# SushiBitsCamera.net
KiCad netlist of a schematic drawn in EAGLE
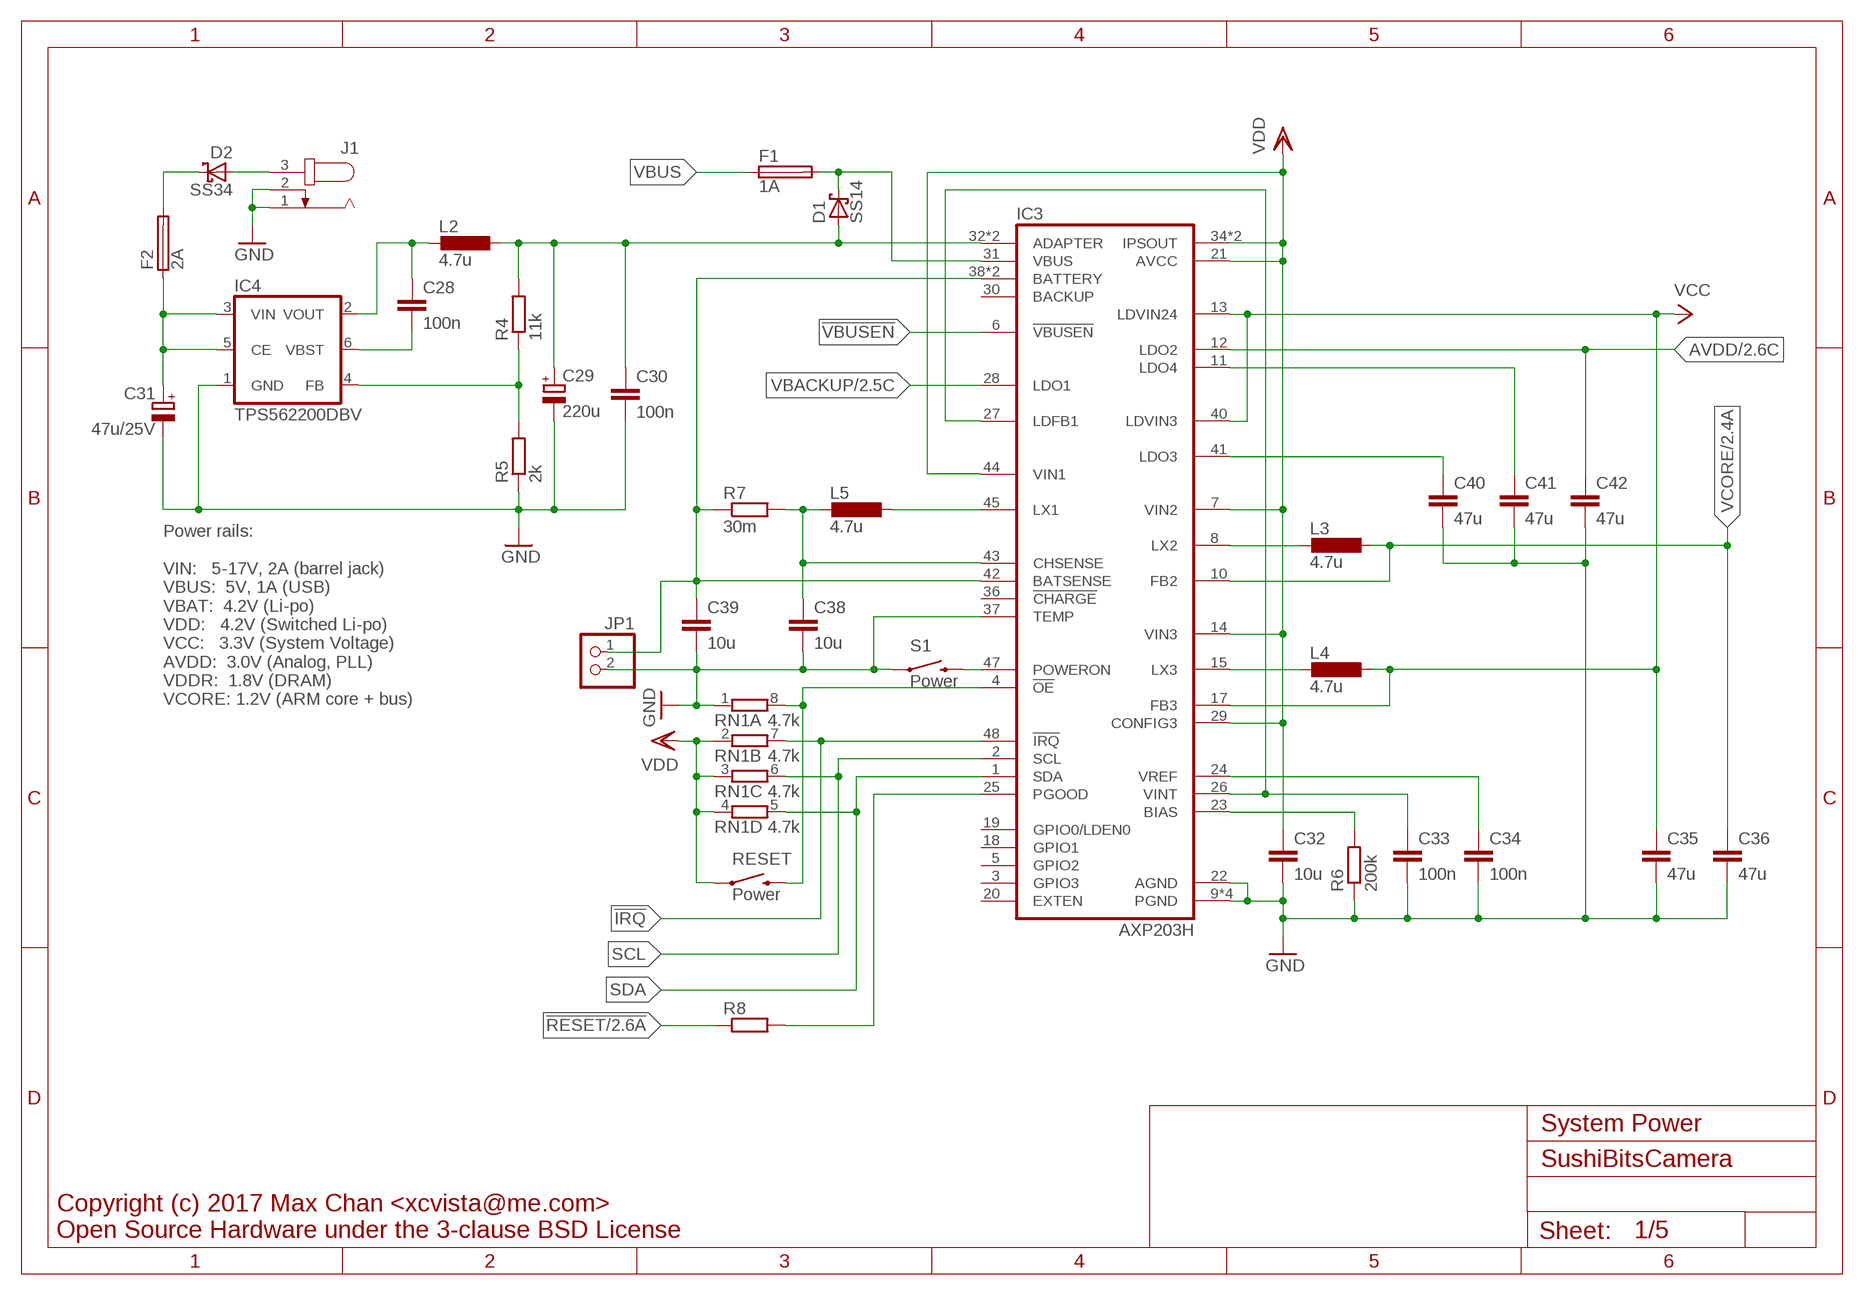
[diagram p0: schematic, sheet 1]
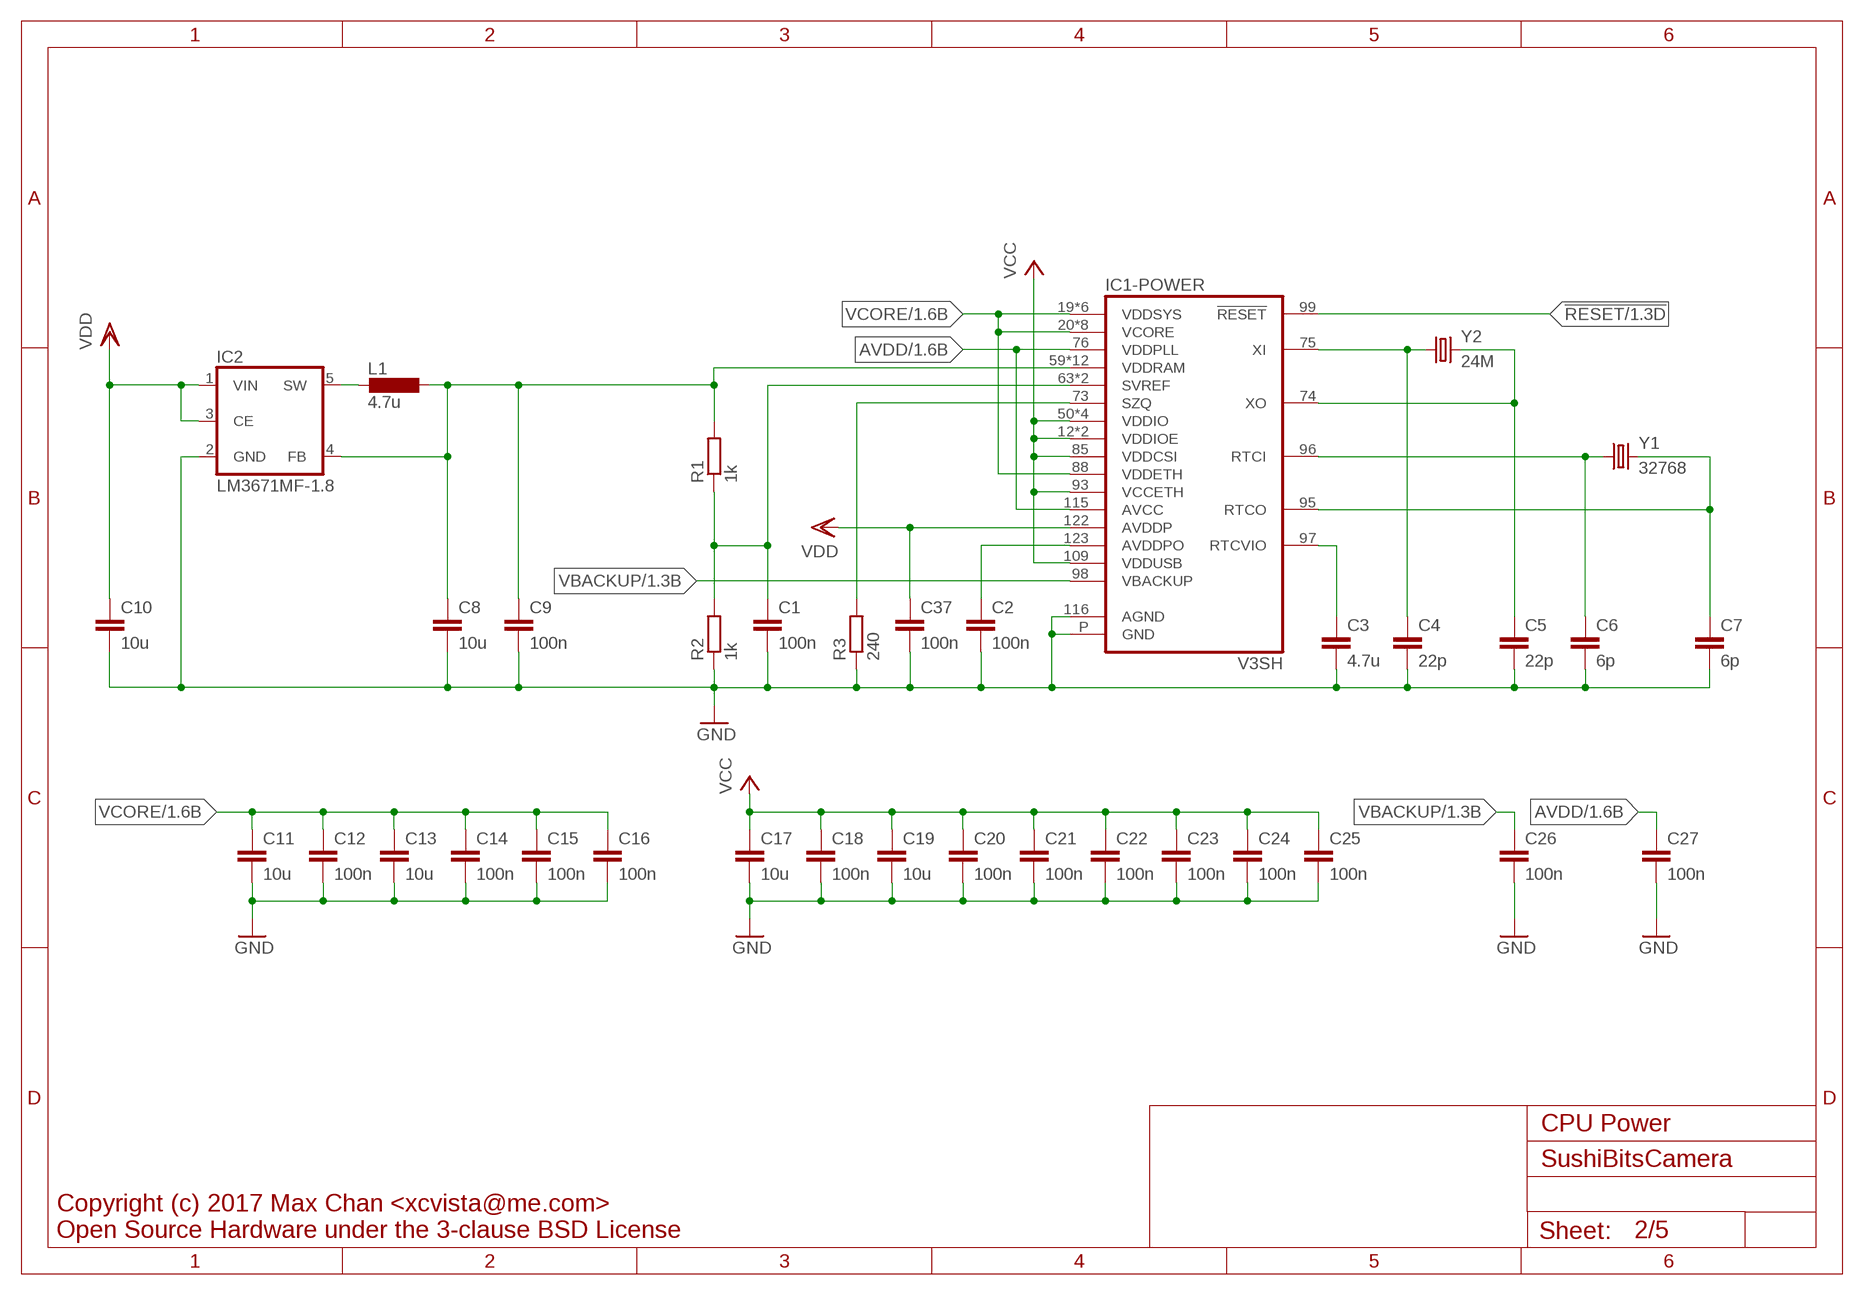
[diagram p1: schematic, sheet 2]
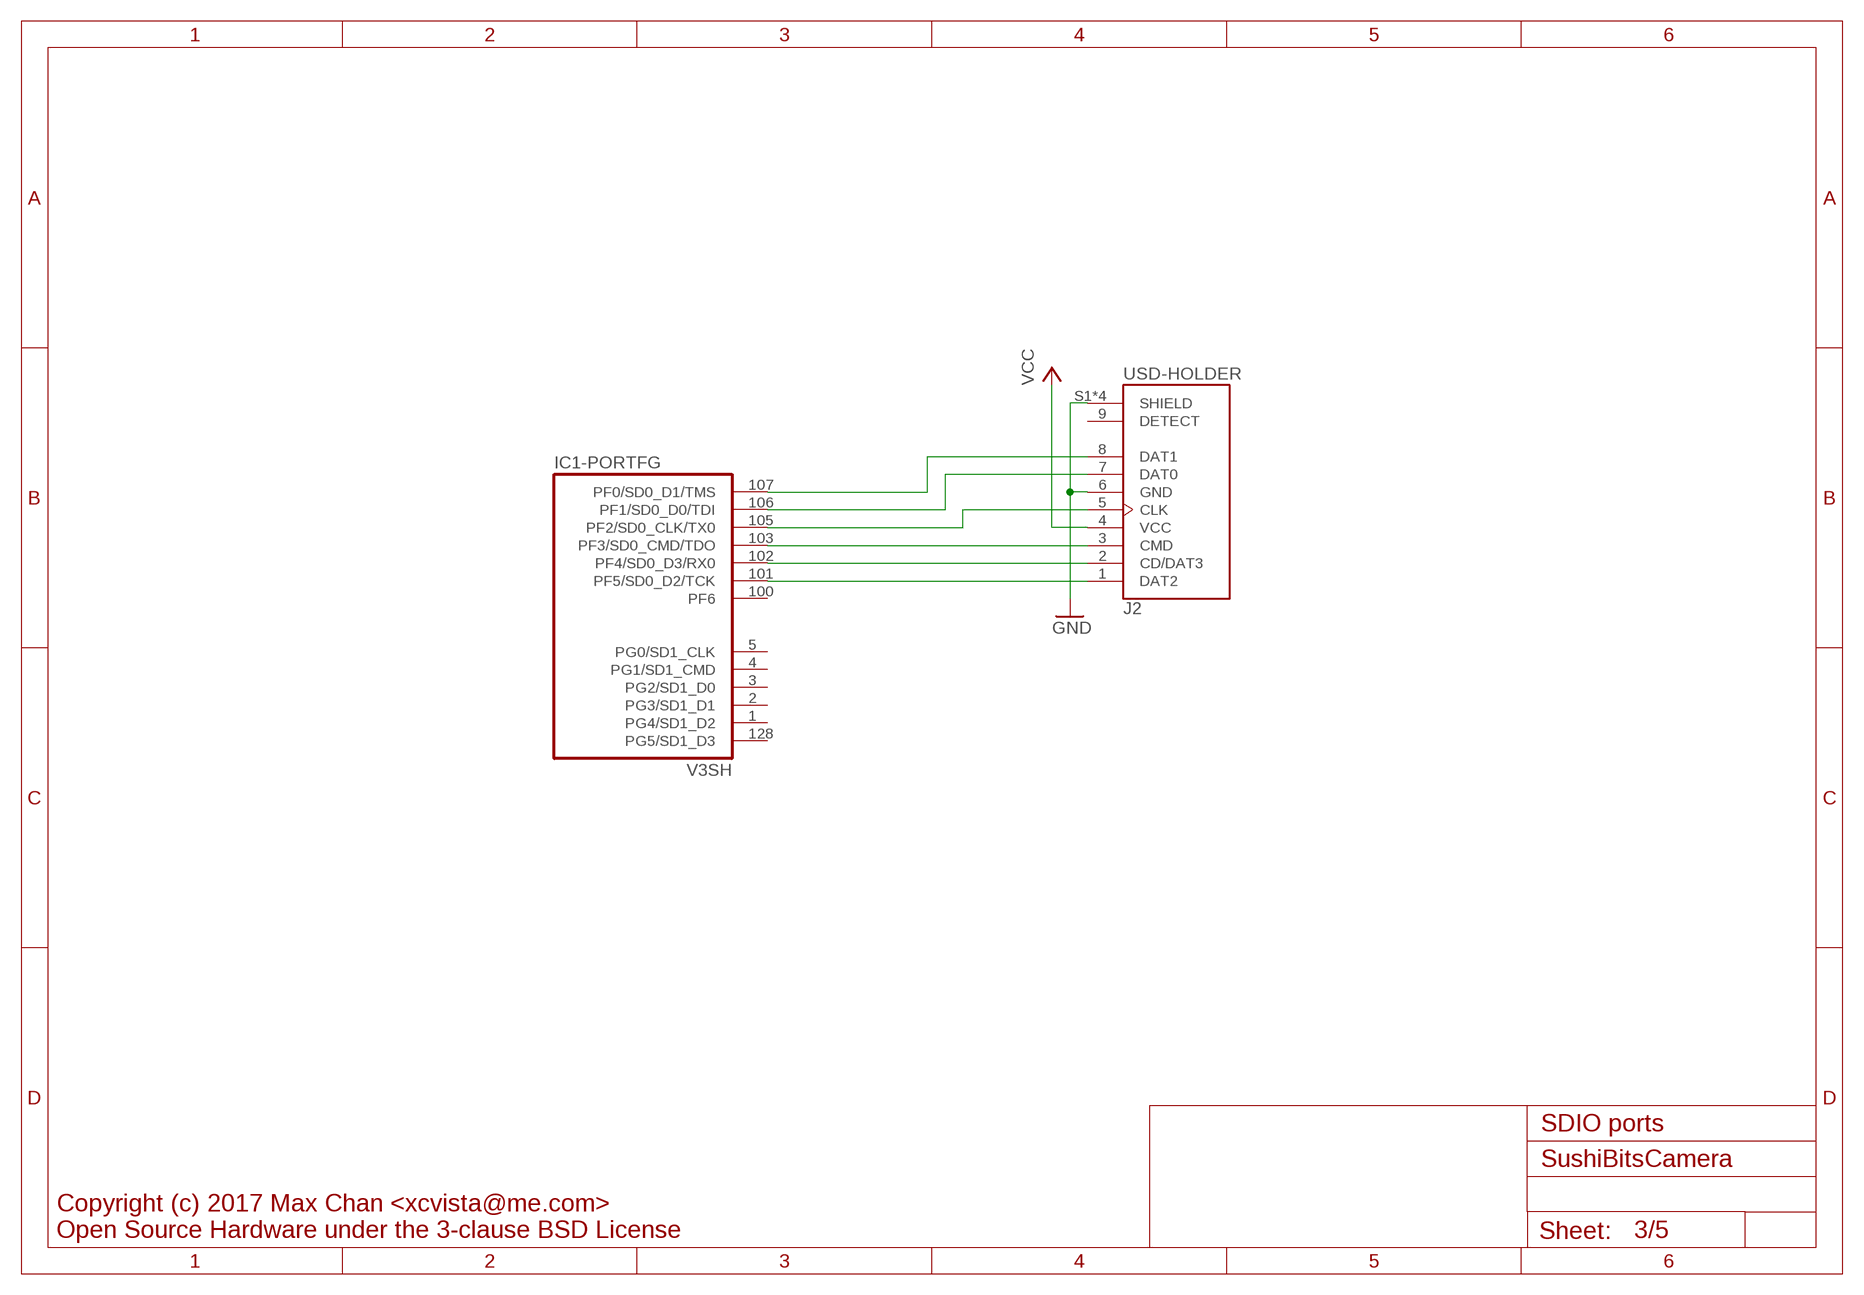
[diagram p2: schematic, sheet 3]
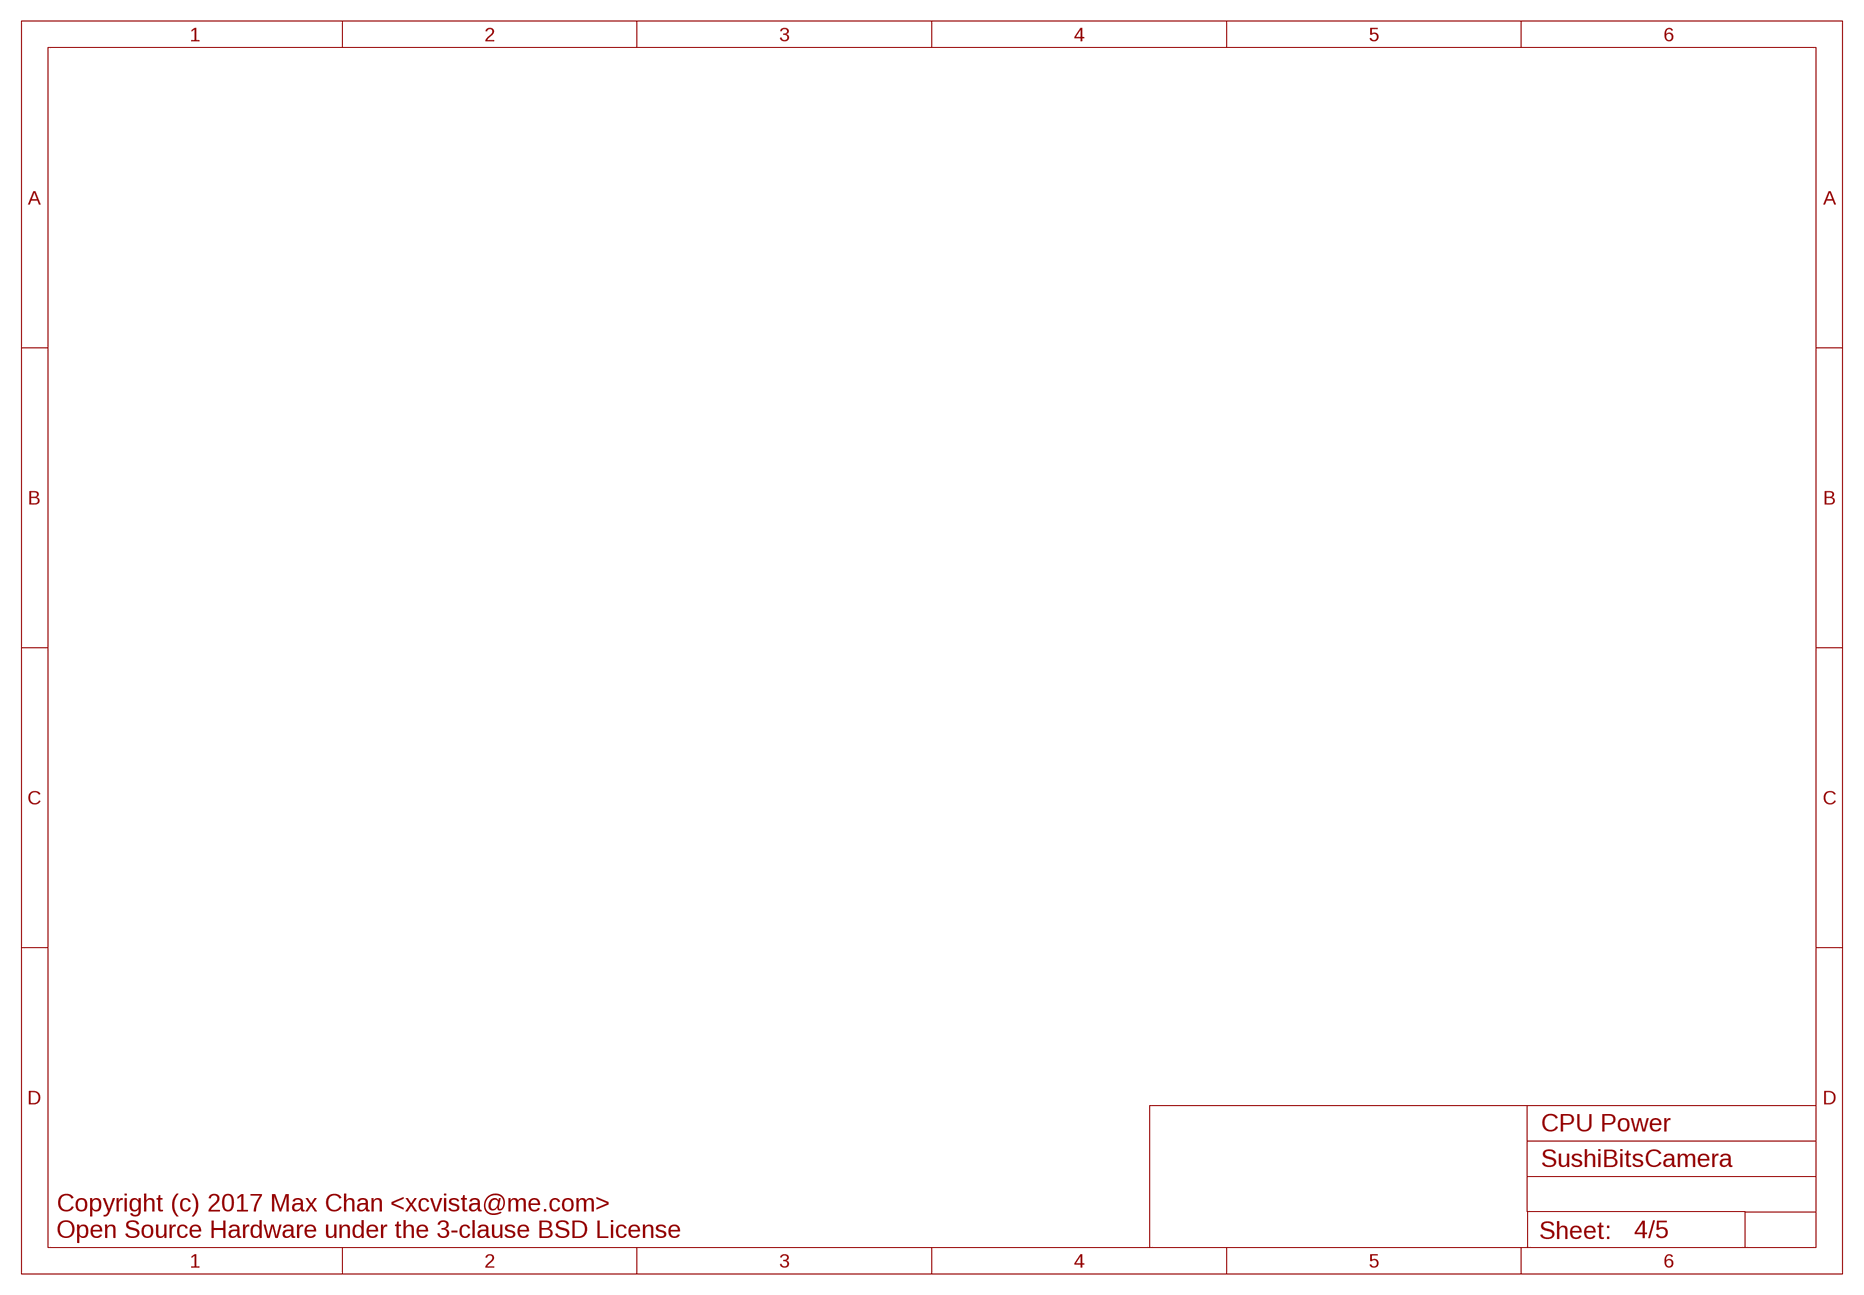
[diagram p3: schematic, sheet 4]
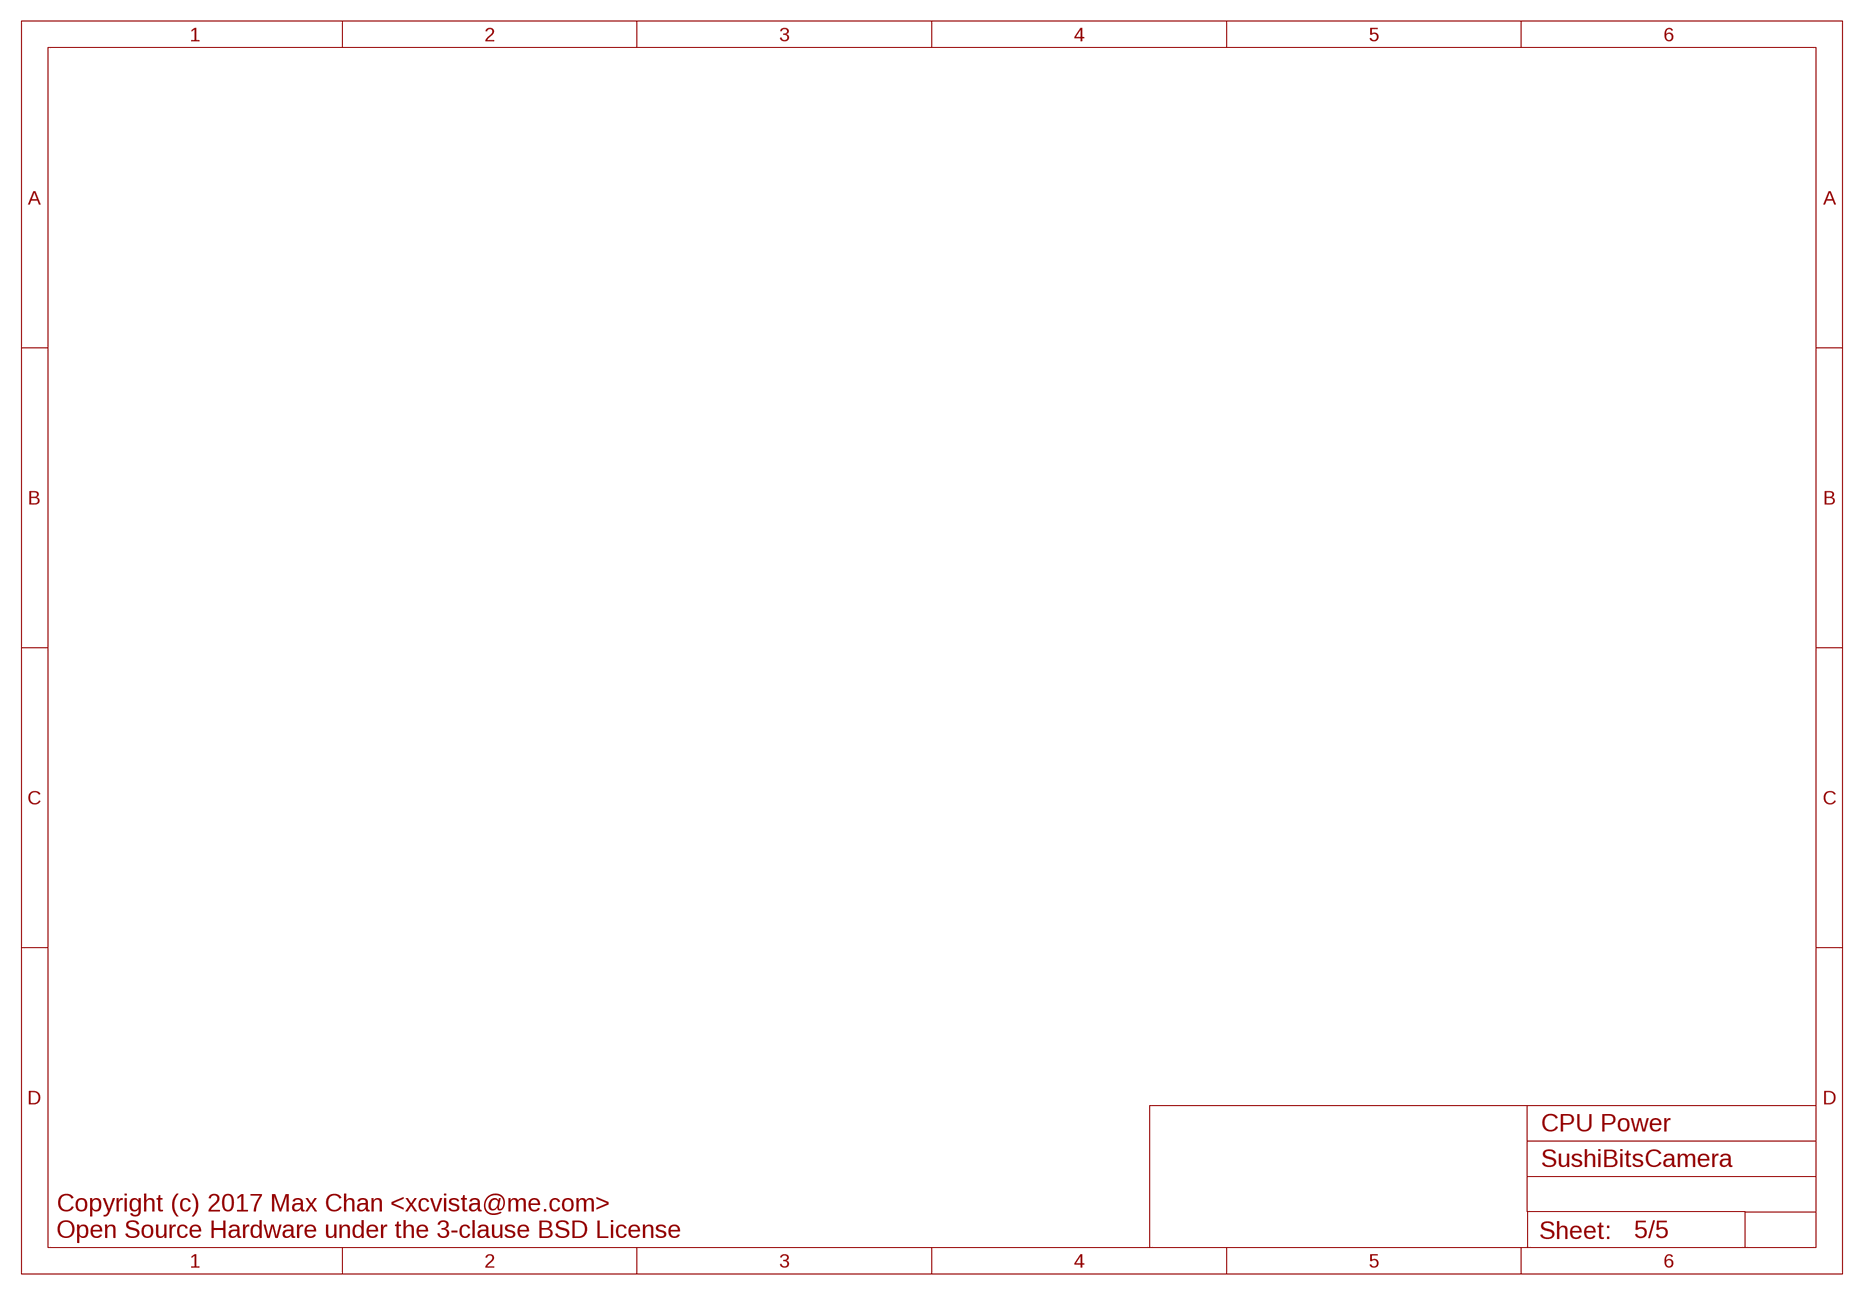
[diagram p4: schematic, sheet 5]

(export (version "E")
  (design (tool "Eeschema 10.0.6"))
  (components
    (comp (ref "C1")
      (value "100n")
      (footprint "eagle-import:C0603")
      (libsource (lib "eagle-import") (part "C-EUC0603"))
    )
    (comp (ref "C2")
      (value "100n")
      (footprint "eagle-import:C0603")
      (libsource (lib "eagle-import") (part "C-EUC0603"))
    )
    (comp (ref "C3")
      (value "4.7u")
      (footprint "eagle-import:C0603")
      (libsource (lib "eagle-import") (part "C-EUC0603"))
    )
    (comp (ref "C4")
      (value "22p")
      (footprint "eagle-import:C0603")
      (libsource (lib "eagle-import") (part "C-EUC0603"))
    )
    (comp (ref "C5")
      (value "22p")
      (footprint "eagle-import:C0603")
      (libsource (lib "eagle-import") (part "C-EUC0603"))
    )
    (comp (ref "C6")
      (value "6p")
      (footprint "eagle-import:C0603")
      (libsource (lib "eagle-import") (part "C-EUC0603"))
    )
    (comp (ref "C7")
      (value "6p")
      (footprint "eagle-import:C0603")
      (libsource (lib "eagle-import") (part "C-EUC0603"))
    )
    (comp (ref "C8")
      (value "10u")
      (footprint "eagle-import:C0603")
      (libsource (lib "eagle-import") (part "C-EUC0603"))
    )
    (comp (ref "C9")
      (value "100n")
      (footprint "eagle-import:C0603")
      (libsource (lib "eagle-import") (part "C-EUC0603"))
    )
    (comp (ref "C10")
      (value "10u")
      (footprint "eagle-import:C0603")
      (libsource (lib "eagle-import") (part "C-EUC0603"))
    )
    (comp (ref "C11")
      (value "10u")
      (footprint "eagle-import:C0603")
      (libsource (lib "eagle-import") (part "C-EUC0603"))
    )
    (comp (ref "C12")
      (value "100n")
      (footprint "eagle-import:C0603")
      (libsource (lib "eagle-import") (part "C-EUC0603"))
    )
    (comp (ref "C13")
      (value "10u")
      (footprint "eagle-import:C0603")
      (libsource (lib "eagle-import") (part "C-EUC0603"))
    )
    (comp (ref "C14")
      (value "100n")
      (footprint "eagle-import:C0603")
      (libsource (lib "eagle-import") (part "C-EUC0603"))
    )
    (comp (ref "C15")
      (value "100n")
      (footprint "eagle-import:C0603")
      (libsource (lib "eagle-import") (part "C-EUC0603"))
    )
    (comp (ref "C16")
      (value "100n")
      (footprint "eagle-import:C0603")
      (libsource (lib "eagle-import") (part "C-EUC0603"))
    )
    (comp (ref "C17")
      (value "10u")
      (footprint "eagle-import:C0603")
      (libsource (lib "eagle-import") (part "C-EUC0603"))
    )
    (comp (ref "C18")
      (value "100n")
      (footprint "eagle-import:C0603")
      (libsource (lib "eagle-import") (part "C-EUC0603"))
    )
    (comp (ref "C19")
      (value "10u")
      (footprint "eagle-import:C0603")
      (libsource (lib "eagle-import") (part "C-EUC0603"))
    )
    (comp (ref "C20")
      (value "100n")
      (footprint "eagle-import:C0603")
      (libsource (lib "eagle-import") (part "C-EUC0603"))
    )
    (comp (ref "C21")
      (value "100n")
      (footprint "eagle-import:C0603")
      (libsource (lib "eagle-import") (part "C-EUC0603"))
    )
    (comp (ref "C22")
      (value "100n")
      (footprint "eagle-import:C0603")
      (libsource (lib "eagle-import") (part "C-EUC0603"))
    )
    (comp (ref "C23")
      (value "100n")
      (footprint "eagle-import:C0603")
      (libsource (lib "eagle-import") (part "C-EUC0603"))
    )
    (comp (ref "C24")
      (value "100n")
      (footprint "eagle-import:C0603")
      (libsource (lib "eagle-import") (part "C-EUC0603"))
    )
    (comp (ref "C25")
      (value "100n")
      (footprint "eagle-import:C0603")
      (libsource (lib "eagle-import") (part "C-EUC0603"))
    )
    (comp (ref "C26")
      (value "100n")
      (footprint "eagle-import:C0603")
      (libsource (lib "eagle-import") (part "C-EUC0603"))
    )
    (comp (ref "C27")
      (value "100n")
      (footprint "eagle-import:C0603")
      (libsource (lib "eagle-import") (part "C-EUC0603"))
    )
    (comp (ref "C37")
      (value "100n")
      (footprint "eagle-import:C0603")
      (libsource (lib "eagle-import") (part "C-EUC0603"))
    )
    (comp (ref "IC1")
      (value "V3SH")
      (footprint "eagle-import:ELQFP128-H")
      (libsource (lib "eagle-import") (part "V3SH"))
    )
    (comp (ref "IC2")
      (value "LM3671MF-1.8")
      (footprint "eagle-import:SOT23-5L")
      (libsource (lib "eagle-import") (part "LM3671?MF-1.8"))
    )
    (comp (ref "L1")
      (value "4.7u")
      (footprint "eagle-import:L5650M")
      (libsource (lib "eagle-import") (part "L-EUL5650M"))
    )
    (comp (ref "R1")
      (value "1k")
      (footprint "eagle-import:R0603")
      (libsource (lib "eagle-import") (part "R-EU_R0603"))
    )
    (comp (ref "R2")
      (value "1k")
      (footprint "eagle-import:R0603")
      (libsource (lib "eagle-import") (part "R-EU_R0603"))
    )
    (comp (ref "R3")
      (value "240")
      (footprint "eagle-import:R0603")
      (libsource (lib "eagle-import") (part "R-EU_R0603"))
    )
    (comp (ref "Y1")
      (value "32768")
      (footprint "eagle-import:CRYSTAL-SMD-3.2X1.5MM")
      (libsource (lib "eagle-import") (part "CRYSTAL3.2X1.5MM"))
    )
    (comp (ref "Y2")
      (value "24M")
      (footprint "eagle-import:CRYSTAL-SMD-5X3")
      (libsource (lib "eagle-import") (part "CRYSTALCRYSTAL-SMD-5X3-16MHZ"))
    )
    (comp (ref "C28")
      (value "100n")
      (footprint "eagle-import:C0603")
      (libsource (lib "eagle-import") (part "C-EUC0603"))
    )
    (comp (ref "C29")
      (value "220u")
      (footprint "eagle-import:SMC_B")
      (libsource (lib "eagle-import") (part "CPOL-EUSMCB"))
    )
    (comp (ref "C30")
      (value "100n")
      (footprint "eagle-import:C0603")
      (libsource (lib "eagle-import") (part "C-EUC0603"))
    )
    (comp (ref "C31")
      (value "47u/25V")
      (footprint "eagle-import:SMC_D")
      (libsource (lib "eagle-import") (part "CPOL-EUSMCD"))
    )
    (comp (ref "C32")
      (value "10u")
      (footprint "eagle-import:C0603")
      (libsource (lib "eagle-import") (part "C-EUC0603"))
    )
    (comp (ref "C33")
      (value "100n")
      (footprint "eagle-import:C0603")
      (libsource (lib "eagle-import") (part "C-EUC0603"))
    )
    (comp (ref "C34")
      (value "100n")
      (footprint "eagle-import:C0603")
      (libsource (lib "eagle-import") (part "C-EUC0603"))
    )
    (comp (ref "C35")
      (value "47u")
      (footprint "eagle-import:C1206")
      (libsource (lib "eagle-import") (part "C-EUC1206"))
    )
    (comp (ref "C36")
      (value "47u")
      (footprint "eagle-import:C1206")
      (libsource (lib "eagle-import") (part "C-EUC1206"))
    )
    (comp (ref "C38")
      (value "10u")
      (footprint "eagle-import:C0603")
      (libsource (lib "eagle-import") (part "C-EUC0603"))
    )
    (comp (ref "C39")
      (value "10u")
      (footprint "eagle-import:C0603")
      (libsource (lib "eagle-import") (part "C-EUC0603"))
    )
    (comp (ref "C40")
      (value "47u")
      (footprint "eagle-import:C1206")
      (libsource (lib "eagle-import") (part "C-EUC1206"))
    )
    (comp (ref "C41")
      (value "47u")
      (footprint "eagle-import:C1206")
      (libsource (lib "eagle-import") (part "C-EUC1206"))
    )
    (comp (ref "C42")
      (value "47u")
      (footprint "eagle-import:C1206")
      (libsource (lib "eagle-import") (part "C-EUC1206"))
    )
    (comp (ref "D1")
      (value "SS14")
      (footprint "eagle-import:DO214AC")
      (libsource (lib "eagle-import") (part "SCHOTTKY-DIODEDO214AC"))
    )
    (comp (ref "D2")
      (value "SS34")
      (footprint "eagle-import:DO214AC")
      (libsource (lib "eagle-import") (part "SCHOTTKY-DIODEDO214AC"))
    )
    (comp (ref "F1")
      (value "1A")
      (footprint "eagle-import:R1206")
      (libsource (lib "eagle-import") (part "FUSER1206"))
    )
    (comp (ref "F2")
      (value "2A")
      (footprint "eagle-import:R1206")
      (libsource (lib "eagle-import") (part "FUSER1206"))
    )
    (comp (ref "IC3")
      (value "AXP203H")
      (footprint "eagle-import:QFN48-6X6-H")
      (libsource (lib "eagle-import") (part "AXP203H"))
    )
    (comp (ref "IC4")
      (value "TPS562200DBV")
      (footprint "eagle-import:SOT23-6L")
      (libsource (lib "eagle-import") (part "TPS56200DBV2"))
    )
    (comp (ref "J1")
      (value "JACK-PLUG0")
      (footprint "eagle-import:SPC4077")
      (libsource (lib "eagle-import") (part "JACK-PLUG0"))
    )
    (comp (ref "JP1")
      (value "PINHD-1X2")
      (footprint "eagle-import:1X02")
      (libsource (lib "eagle-import") (part "PINHD-1X2"))
    )
    (comp (ref "L2")
      (value "4.7u")
      (footprint "eagle-import:L5650M")
      (libsource (lib "eagle-import") (part "L-EUL5650M"))
    )
    (comp (ref "L3")
      (value "4.7u")
      (footprint "eagle-import:L5650M")
      (libsource (lib "eagle-import") (part "L-EUL5650M"))
    )
    (comp (ref "L4")
      (value "4.7u")
      (footprint "eagle-import:L5650M")
      (libsource (lib "eagle-import") (part "L-EUL5650M"))
    )
    (comp (ref "L5")
      (value "4.7u")
      (footprint "eagle-import:L5650M")
      (libsource (lib "eagle-import") (part "L-EUL5650M"))
    )
    (comp (ref "R4")
      (value "11k")
      (footprint "eagle-import:R0603")
      (libsource (lib "eagle-import") (part "R-EU_R0603"))
    )
    (comp (ref "R5")
      (value "2k")
      (footprint "eagle-import:R0603")
      (libsource (lib "eagle-import") (part "R-EU_R0603"))
    )
    (comp (ref "R6")
      (value "200k")
      (footprint "eagle-import:R0603")
      (libsource (lib "eagle-import") (part "R-EU_R0603"))
    )
    (comp (ref "R7")
      (value "30m")
      (footprint "eagle-import:R2512")
      (libsource (lib "eagle-import") (part "R-EU_R2512"))
    )
    (comp (ref "R8")
      (value "R-EU_R0603")
      (footprint "eagle-import:R0603")
      (libsource (lib "eagle-import") (part "R-EU_R0603"))
    )
    (comp (ref "RESET")
      (value "Power")
      (footprint "eagle-import:TACTILE-PTH-SIDEEZ")
      (libsource (lib "eagle-import") (part "SWITCH-MOMENTARY-2SIDE_EZ"))
    )
    (comp (ref "RN1")
      (value "4.7k")
      (footprint "eagle-import:EXB38V")
      (libsource (lib "eagle-import") (part "4R-NEXB38V"))
    )
    (comp (ref "S1")
      (value "Power")
      (footprint "eagle-import:TACTILE-PTH-SIDEEZ")
      (libsource (lib "eagle-import") (part "SWITCH-MOMENTARY-2SIDE_EZ"))
    )
    (comp (ref "J2")
      (value "USD-HOLDER")
      (footprint "eagle-import:USD-HOLDER")
      (libsource (lib "eagle-import") (part "USD-HOLDER"))
    )
  )
  (nets
    (net (code "1") (name "AVDD") (class "Default")
      (node (ref "C27") (pin "1") (pinfunction "1_1") (pintype "passive"))
      (node (ref "C42") (pin "1") (pinfunction "1_1") (pintype "passive"))
      (node (ref "IC1") (pin "115") (pinfunction "AVCC_115") (pintype "bidirectional"))
      (node (ref "IC1") (pin "76") (pinfunction "VDDPLL_76") (pintype "bidirectional"))
      (node (ref "IC3") (pin "12") (pinfunction "LDO2_12") (pintype "bidirectional"))
    )
    (net (code "2") (name "GND") (class "Default")
      (node (ref "C1") (pin "2") (pinfunction "2_2") (pintype "passive"))
      (node (ref "C10") (pin "2") (pinfunction "2_2") (pintype "passive"))
      (node (ref "C11") (pin "2") (pinfunction "2_2") (pintype "passive"))
      (node (ref "C12") (pin "2") (pinfunction "2_2") (pintype "passive"))
      (node (ref "C13") (pin "2") (pinfunction "2_2") (pintype "passive"))
      (node (ref "C14") (pin "2") (pinfunction "2_2") (pintype "passive"))
      (node (ref "C15") (pin "2") (pinfunction "2_2") (pintype "passive"))
      (node (ref "C16") (pin "2") (pinfunction "2_2") (pintype "passive"))
      (node (ref "C17") (pin "2") (pinfunction "2_2") (pintype "passive"))
      (node (ref "C18") (pin "2") (pinfunction "2_2") (pintype "passive"))
      (node (ref "C19") (pin "2") (pinfunction "2_2") (pintype "passive"))
      (node (ref "C2") (pin "2") (pinfunction "2_2") (pintype "passive"))
      (node (ref "C20") (pin "2") (pinfunction "2_2") (pintype "passive"))
      (node (ref "C21") (pin "2") (pinfunction "2_2") (pintype "passive"))
      (node (ref "C22") (pin "2") (pinfunction "2_2") (pintype "passive"))
      (node (ref "C23") (pin "2") (pinfunction "2_2") (pintype "passive"))
      (node (ref "C24") (pin "2") (pinfunction "2_2") (pintype "passive"))
      (node (ref "C25") (pin "2") (pinfunction "2_2") (pintype "passive"))
      (node (ref "C26") (pin "2") (pinfunction "2_2") (pintype "passive"))
      (node (ref "C27") (pin "2") (pinfunction "2_2") (pintype "passive"))
      (node (ref "C29") (pin "-") (pinfunction "-_-") (pintype "passive"))
      (node (ref "C3") (pin "2") (pinfunction "2_2") (pintype "passive"))
      (node (ref "C30") (pin "2") (pinfunction "2_2") (pintype "passive"))
      (node (ref "C31") (pin "-") (pinfunction "-_-") (pintype "passive"))
      (node (ref "C32") (pin "2") (pinfunction "2_2") (pintype "passive"))
      (node (ref "C33") (pin "2") (pinfunction "2_2") (pintype "passive"))
      (node (ref "C34") (pin "2") (pinfunction "2_2") (pintype "passive"))
      (node (ref "C35") (pin "2") (pinfunction "2_2") (pintype "passive"))
      (node (ref "C36") (pin "2") (pinfunction "2_2") (pintype "passive"))
      (node (ref "C37") (pin "2") (pinfunction "2_2") (pintype "passive"))
      (node (ref "C38") (pin "2") (pinfunction "2_2") (pintype "passive"))
      (node (ref "C39") (pin "2") (pinfunction "2_2") (pintype "passive"))
      (node (ref "C4") (pin "2") (pinfunction "2_2") (pintype "passive"))
      (node (ref "C40") (pin "2") (pinfunction "2_2") (pintype "passive"))
      (node (ref "C41") (pin "2") (pinfunction "2_2") (pintype "passive"))
      (node (ref "C42") (pin "2") (pinfunction "2_2") (pintype "passive"))
      (node (ref "C5") (pin "2") (pinfunction "2_2") (pintype "passive"))
      (node (ref "C6") (pin "2") (pinfunction "2_2") (pintype "passive"))
      (node (ref "C7") (pin "2") (pinfunction "2_2") (pintype "passive"))
      (node (ref "C8") (pin "2") (pinfunction "2_2") (pintype "passive"))
      (node (ref "C9") (pin "2") (pinfunction "2_2") (pintype "passive"))
      (node (ref "IC1") (pin "116") (pinfunction "AGND_116") (pintype "bidirectional"))
      (node (ref "IC1") (pin "P") (pinfunction "GND_P") (pintype "bidirectional"))
      (node (ref "IC2") (pin "2") (pinfunction "GND_2") (pintype "passive"))
      (node (ref "IC3") (pin "16") (pinfunction "PGND_16") (pintype "bidirectional"))
      (node (ref "IC3") (pin "22") (pinfunction "AGND_22") (pintype "bidirectional"))
      (node (ref "IC3") (pin "37") (pinfunction "TEMP_37") (pintype "bidirectional"))
      (node (ref "IC3") (pin "46") (pinfunction "PGND_46") (pintype "bidirectional"))
      (node (ref "IC3") (pin "9") (pinfunction "PGND_9") (pintype "bidirectional"))
      (node (ref "IC3") (pin "P") (pinfunction "PGND_P") (pintype "bidirectional"))
      (node (ref "IC4") (pin "1") (pinfunction "GND_1") (pintype "passive"))
      (node (ref "J1") (pin "1") (pinfunction "1_1") (pintype "passive"))
      (node (ref "J1") (pin "2") (pinfunction "2_2") (pintype "passive"))
      (node (ref "J2") (pin "6") (pinfunction "GND_6") (pintype "power_in"))
      (node (ref "J2") (pin "S1") (pinfunction "SHIELD_S1") (pintype "passive"))
      (node (ref "J2") (pin "S2") (pinfunction "SHIELD_S2") (pintype "passive"))
      (node (ref "J2") (pin "S3") (pinfunction "SHIELD_S3") (pintype "passive"))
      (node (ref "J2") (pin "S4") (pinfunction "SHIELD_S4") (pintype "passive"))
      (node (ref "JP1") (pin "2") (pinfunction "2_2") (pintype "passive"))
      (node (ref "R2") (pin "1") (pinfunction "1_1") (pintype "passive"))
      (node (ref "R3") (pin "1") (pinfunction "1_1") (pintype "passive"))
      (node (ref "R5") (pin "1") (pinfunction "1_1") (pintype "passive"))
      (node (ref "R6") (pin "1") (pinfunction "1_1") (pintype "passive"))
      (node (ref "RN1") (pin "1") (pinfunction "1_1") (pintype "passive"))
      (node (ref "S1") (pin "1") (pinfunction "1_1") (pintype "passive"))
    )
    (net (code "3") (name "Net-(C1-Pad1)") (class "Default")
      (node (ref "C1") (pin "1") (pinfunction "1_1") (pintype "passive"))
      (node (ref "IC1") (pin "63") (pinfunction "SVREF_63") (pintype "bidirectional"))
      (node (ref "IC1") (pin "71") (pinfunction "SVREF_71") (pintype "bidirectional"))
      (node (ref "R1") (pin "1") (pinfunction "1_1") (pintype "passive"))
      (node (ref "R2") (pin "2") (pinfunction "2_2") (pintype "passive"))
    )
    (net (code "4") (name "Net-(C29-Pad+)") (class "Default")
      (node (ref "C29") (pin "+") (pinfunction "+_+") (pintype "passive"))
      (node (ref "C30") (pin "1") (pinfunction "1_1") (pintype "passive"))
      (node (ref "D1") (pin "A") (pinfunction "A_A") (pintype "passive"))
      (node (ref "IC3") (pin "32") (pinfunction "ADAPTER_32") (pintype "bidirectional"))
      (node (ref "IC3") (pin "33") (pinfunction "ADAPTER_33") (pintype "bidirectional"))
      (node (ref "L2") (pin "1") (pinfunction "1_1") (pintype "passive"))
      (node (ref "R4") (pin "2") (pinfunction "2_2") (pintype "passive"))
    )
    (net (code "5") (name "Net-(D2-PadA)") (class "Default")
      (node (ref "D2") (pin "A") (pinfunction "A_A") (pintype "passive"))
      (node (ref "J1") (pin "3") (pinfunction "3_3") (pintype "passive"))
    )
    (net (code "6") (name "Net-(D2-PadC)") (class "Default")
      (node (ref "D2") (pin "C") (pinfunction "C_C") (pintype "passive"))
      (node (ref "F2") (pin "2") (pinfunction "2_2") (pintype "passive"))
    )
    (net (code "7") (name "Net-(IC1E-PF0{slash}SD0_D1{slash}TMS)") (class "Default")
      (node (ref "IC1") (pin "107") (pinfunction "PF0/SD0_D1/TMS_107") (pintype "bidirectional"))
      (node (ref "J2") (pin "8") (pinfunction "DAT1_8") (pintype "bidirectional"))
    )
    (net (code "8") (name "Net-(IC1E-PF1{slash}SD0_D0{slash}TDI)") (class "Default")
      (node (ref "IC1") (pin "106") (pinfunction "PF1/SD0_D0/TDI_106") (pintype "bidirectional"))
      (node (ref "J2") (pin "7") (pinfunction "DAT0_7") (pintype "bidirectional"))
    )
    (net (code "9") (name "Net-(IC1E-PF2{slash}SD0_CLK{slash}TX0)") (class "Default")
      (node (ref "IC1") (pin "105") (pinfunction "PF2/SD0_CLK/TX0_105") (pintype "bidirectional"))
      (node (ref "J2") (pin "5") (pinfunction "CLK_5") (pintype "input"))
    )
    (net (code "10") (name "Net-(IC1E-PF3{slash}SD0_CMD{slash}TDO)") (class "Default")
      (node (ref "IC1") (pin "103") (pinfunction "PF3/SD0_CMD/TDO_103") (pintype "bidirectional"))
      (node (ref "J2") (pin "3") (pinfunction "CMD_3") (pintype "bidirectional"))
    )
    (net (code "11") (name "Net-(IC1E-PF4{slash}SD0_D3{slash}RX0)") (class "Default")
      (node (ref "IC1") (pin "102") (pinfunction "PF4/SD0_D3/RX0_102") (pintype "bidirectional"))
      (node (ref "J2") (pin "2") (pinfunction "CD/DAT3_2") (pintype "bidirectional"))
    )
    (net (code "12") (name "Net-(IC1E-PF5{slash}SD0_D2{slash}TCK)") (class "Default")
      (node (ref "IC1") (pin "101") (pinfunction "PF5/SD0_D2/TCK_101") (pintype "bidirectional"))
      (node (ref "J2") (pin "1") (pinfunction "DAT2_1") (pintype "bidirectional"))
    )
    (net (code "13") (name "Net-(IC1F-AVDDPO)") (class "Default")
      (node (ref "C2") (pin "1") (pinfunction "1_1") (pintype "passive"))
      (node (ref "IC1") (pin "123") (pinfunction "AVDDPO_123") (pintype "bidirectional"))
    )
    (net (code "14") (name "Net-(IC1F-RTCI)") (class "Default")
      (node (ref "C6") (pin "1") (pinfunction "1_1") (pintype "passive"))
      (node (ref "IC1") (pin "96") (pinfunction "RTCI_96") (pintype "bidirectional"))
      (node (ref "Y1") (pin "P$1") (pinfunction "1_P$1") (pintype "passive"))
    )
    (net (code "15") (name "Net-(IC1F-RTCO)") (class "Default")
      (node (ref "C7") (pin "1") (pinfunction "1_1") (pintype "passive"))
      (node (ref "IC1") (pin "95") (pinfunction "RTCO_95") (pintype "bidirectional"))
      (node (ref "Y1") (pin "P$2") (pinfunction "2_P$2") (pintype "passive"))
    )
    (net (code "16") (name "Net-(IC1F-RTCVIO)") (class "Default")
      (node (ref "C3") (pin "1") (pinfunction "1_1") (pintype "passive"))
      (node (ref "IC1") (pin "97") (pinfunction "RTCVIO_97") (pintype "bidirectional"))
    )
    (net (code "17") (name "Net-(IC1F-SZQ)") (class "Default")
      (node (ref "IC1") (pin "73") (pinfunction "SZQ_73") (pintype "bidirectional"))
      (node (ref "R3") (pin "2") (pinfunction "2_2") (pintype "passive"))
    )
    (net (code "18") (name "Net-(IC1F-XI)") (class "Default")
      (node (ref "C4") (pin "1") (pinfunction "1_1") (pintype "passive"))
      (node (ref "IC1") (pin "75") (pinfunction "XI_75") (pintype "bidirectional"))
      (node (ref "Y2") (pin "1") (pinfunction "1_1") (pintype "passive"))
    )
    (net (code "19") (name "Net-(IC1F-XO)") (class "Default")
      (node (ref "C5") (pin "1") (pinfunction "1_1") (pintype "passive"))
      (node (ref "IC1") (pin "74") (pinfunction "XO_74") (pintype "bidirectional"))
      (node (ref "Y2") (pin "3") (pinfunction "2_3") (pintype "passive"))
    )
    (net (code "20") (name "Net-(IC2-FB)") (class "Default")
      (node (ref "C8") (pin "1") (pinfunction "1_1") (pintype "passive"))
      (node (ref "C9") (pin "1") (pinfunction "1_1") (pintype "passive"))
      (node (ref "IC1") (pin "59") (pinfunction "VDDRAM_59") (pintype "bidirectional"))
      (node (ref "IC1") (pin "60") (pinfunction "VDDRAM_60") (pintype "bidirectional"))
      (node (ref "IC1") (pin "61") (pinfunction "VDDRAM_61") (pintype "bidirectional"))
      (node (ref "IC1") (pin "62") (pinfunction "VDDRAM_62") (pintype "bidirectional"))
      (node (ref "IC1") (pin "65") (pinfunction "VDDRAM_65") (pintype "bidirectional"))
      (node (ref "IC1") (pin "66") (pinfunction "VDDRAM_66") (pintype "bidirectional"))
      (node (ref "IC1") (pin "67") (pinfunction "VDDRAM_67") (pintype "bidirectional"))
      (node (ref "IC1") (pin "68") (pinfunction "VDDRAM_68") (pintype "bidirectional"))
      (node (ref "IC1") (pin "69") (pinfunction "VDDRAM_69") (pintype "bidirectional"))
      (node (ref "IC1") (pin "70") (pinfunction "VDDRAM_70") (pintype "bidirectional"))
      (node (ref "IC1") (pin "72") (pinfunction "VDDRAM_72") (pintype "bidirectional"))
      (node (ref "IC1") (pin "79") (pinfunction "VDDRAM_79") (pintype "bidirectional"))
      (node (ref "IC2") (pin "4") (pinfunction "FB_4") (pintype "input"))
      (node (ref "L1") (pin "1") (pinfunction "1_1") (pintype "passive"))
      (node (ref "R1") (pin "2") (pinfunction "2_2") (pintype "passive"))
    )
    (net (code "21") (name "Net-(IC2-SW)") (class "Default")
      (node (ref "IC2") (pin "5") (pinfunction "SW_5") (pintype "passive"))
      (node (ref "L1") (pin "2") (pinfunction "2_2") (pintype "passive"))
    )
    (net (code "22") (name "Net-(IC3-BATSENSE)") (class "Default")
      (node (ref "C39") (pin "1") (pinfunction "1_1") (pintype "passive"))
      (node (ref "IC3") (pin "38") (pinfunction "BATTERY_38") (pintype "bidirectional"))
      (node (ref "IC3") (pin "39") (pinfunction "BATTERY_39") (pintype "bidirectional"))
      (node (ref "IC3") (pin "42") (pinfunction "BATSENSE_42") (pintype "bidirectional"))
      (node (ref "JP1") (pin "1") (pinfunction "1_1") (pintype "passive"))
      (node (ref "R7") (pin "1") (pinfunction "1_1") (pintype "passive"))
    )
    (net (code "23") (name "Net-(IC3-BIAS)") (class "Default")
      (node (ref "IC3") (pin "23") (pinfunction "BIAS_23") (pintype "bidirectional"))
      (node (ref "R6") (pin "2") (pinfunction "2_2") (pintype "passive"))
    )
    (net (code "24") (name "Net-(IC3-CHSENSE)") (class "Default")
      (node (ref "C38") (pin "1") (pinfunction "1_1") (pintype "passive"))
      (node (ref "IC3") (pin "43") (pinfunction "CHSENSE_43") (pintype "bidirectional"))
      (node (ref "L5") (pin "2") (pinfunction "2_2") (pintype "passive"))
      (node (ref "R7") (pin "2") (pinfunction "2_2") (pintype "passive"))
    )
    (net (code "25") (name "Net-(IC3-LDFB1)") (class "Default")
      (node (ref "C33") (pin "1") (pinfunction "1_1") (pintype "passive"))
      (node (ref "IC3") (pin "26") (pinfunction "VINT_26") (pintype "bidirectional"))
      (node (ref "IC3") (pin "27") (pinfunction "LDFB1_27") (pintype "bidirectional"))
    )
    (net (code "26") (name "Net-(IC3-LDO3)") (class "Default")
      (node (ref "C40") (pin "1") (pinfunction "1_1") (pintype "passive"))
      (node (ref "IC3") (pin "41") (pinfunction "LDO3_41") (pintype "bidirectional"))
    )
    (net (code "27") (name "Net-(IC3-LDO4)") (class "Default")
      (node (ref "C41") (pin "1") (pinfunction "1_1") (pintype "passive"))
      (node (ref "IC3") (pin "11") (pinfunction "LDO4_11") (pintype "bidirectional"))
    )
    (net (code "28") (name "Net-(IC3-LX1)") (class "Default")
      (node (ref "IC3") (pin "45") (pinfunction "LX1_45") (pintype "bidirectional"))
      (node (ref "L5") (pin "1") (pinfunction "1_1") (pintype "passive"))
    )
    (net (code "29") (name "Net-(IC3-LX2)") (class "Default")
      (node (ref "IC3") (pin "8") (pinfunction "LX2_8") (pintype "bidirectional"))
      (node (ref "L3") (pin "2") (pinfunction "2_2") (pintype "passive"))
    )
    (net (code "30") (name "Net-(IC3-LX3)") (class "Default")
      (node (ref "IC3") (pin "15") (pinfunction "LX3_15") (pintype "bidirectional"))
      (node (ref "L4") (pin "2") (pinfunction "2_2") (pintype "passive"))
    )
    (net (code "31") (name "Net-(IC3-PGOOD)") (class "Default")
      (node (ref "IC3") (pin "25") (pinfunction "PGOOD_25") (pintype "bidirectional"))
      (node (ref "R8") (pin "2") (pinfunction "2_2") (pintype "passive"))
    )
    (net (code "32") (name "Net-(IC3-POWERON)") (class "Default")
      (node (ref "IC3") (pin "47") (pinfunction "POWERON_47") (pintype "bidirectional"))
      (node (ref "S1") (pin "2") (pinfunction "2_2") (pintype "passive"))
    )
    (net (code "33") (name "Net-(IC3-VBUS)") (class "Default")
      (node (ref "D1") (pin "C") (pinfunction "C_C") (pintype "passive"))
      (node (ref "F1") (pin "2") (pinfunction "2_2") (pintype "passive"))
      (node (ref "IC3") (pin "31") (pinfunction "VBUS_31") (pintype "bidirectional"))
    )
    (net (code "34") (name "Net-(IC3-VREF)") (class "Default")
      (node (ref "C34") (pin "1") (pinfunction "1_1") (pintype "passive"))
      (node (ref "IC3") (pin "24") (pinfunction "VREF_24") (pintype "bidirectional"))
    )
    (net (code "35") (name "Net-(IC3-~{OE})") (class "Default")
      (node (ref "IC3") (pin "4") (pinfunction "~{OE}_4") (pintype "bidirectional"))
      (node (ref "RESET") (pin "2") (pinfunction "2_2") (pintype "passive"))
      (node (ref "RN1") (pin "8") (pinfunction "2_8") (pintype "passive"))
    )
    (net (code "36") (name "Net-(IC4-CE)") (class "Default")
      (node (ref "C31") (pin "+") (pinfunction "+_+") (pintype "passive"))
      (node (ref "F2") (pin "1") (pinfunction "1_1") (pintype "passive"))
      (node (ref "IC4") (pin "3") (pinfunction "VIN_3") (pintype "input"))
      (node (ref "IC4") (pin "5") (pinfunction "CE_5") (pintype "input"))
    )
    (net (code "37") (name "Net-(IC4-FB)") (class "Default")
      (node (ref "IC4") (pin "4") (pinfunction "FB_4") (pintype "input"))
      (node (ref "R4") (pin "1") (pinfunction "1_1") (pintype "passive"))
      (node (ref "R5") (pin "2") (pinfunction "2_2") (pintype "passive"))
    )
    (net (code "38") (name "Net-(IC4-VBST)") (class "Default")
      (node (ref "C28") (pin "2") (pinfunction "2_2") (pintype "passive"))
      (node (ref "IC4") (pin "6") (pinfunction "VBST_6") (pintype "passive"))
    )
    (net (code "39") (name "Net-(IC4-VOUT)") (class "Default")
      (node (ref "C28") (pin "1") (pinfunction "1_1") (pintype "passive"))
      (node (ref "IC4") (pin "2") (pinfunction "VOUT_2") (pintype "passive"))
      (node (ref "L2") (pin "2") (pinfunction "2_2") (pintype "passive"))
    )
    (net (code "40") (name "SCL") (class "Default")
      (node (ref "IC3") (pin "2") (pinfunction "SCL_2") (pintype "bidirectional"))
      (node (ref "RN1") (pin "6") (pinfunction "2_6") (pintype "passive"))
    )
    (net (code "41") (name "SDA") (class "Default")
      (node (ref "IC3") (pin "1") (pinfunction "SDA_1") (pintype "bidirectional"))
      (node (ref "RN1") (pin "5") (pinfunction "2_5") (pintype "passive"))
    )
    (net (code "42") (name "VBACKUP") (class "Default")
      (node (ref "C26") (pin "1") (pinfunction "1_1") (pintype "passive"))
      (node (ref "IC1") (pin "98") (pinfunction "VBACKUP_98") (pintype "bidirectional"))
      (node (ref "IC3") (pin "28") (pinfunction "LDO1_28") (pintype "bidirectional"))
    )
    (net (code "43") (name "VBUS") (class "Default")
      (node (ref "F1") (pin "1") (pinfunction "1_1") (pintype "passive"))
    )
    (net (code "44") (name "VCC") (class "Default")
      (node (ref "C17") (pin "1") (pinfunction "1_1") (pintype "passive"))
      (node (ref "C18") (pin "1") (pinfunction "1_1") (pintype "passive"))
      (node (ref "C19") (pin "1") (pinfunction "1_1") (pintype "passive"))
      (node (ref "C20") (pin "1") (pinfunction "1_1") (pintype "passive"))
      (node (ref "C21") (pin "1") (pinfunction "1_1") (pintype "passive"))
      (node (ref "C22") (pin "1") (pinfunction "1_1") (pintype "passive"))
      (node (ref "C23") (pin "1") (pinfunction "1_1") (pintype "passive"))
      (node (ref "C24") (pin "1") (pinfunction "1_1") (pintype "passive"))
      (node (ref "C25") (pin "1") (pinfunction "1_1") (pintype "passive"))
      (node (ref "C35") (pin "1") (pinfunction "1_1") (pintype "passive"))
      (node (ref "IC1") (pin "104") (pinfunction "VDDIO_104") (pintype "bidirectional"))
      (node (ref "IC1") (pin "109") (pinfunction "VDDUSB_109") (pintype "bidirectional"))
      (node (ref "IC1") (pin "12") (pinfunction "VDDIOE_12") (pintype "bidirectional"))
      (node (ref "IC1") (pin "127") (pinfunction "VDDIO_127") (pintype "bidirectional"))
      (node (ref "IC1") (pin "29") (pinfunction "VDDIOE_29") (pintype "bidirectional"))
      (node (ref "IC1") (pin "50") (pinfunction "VDDIO_50") (pintype "bidirectional"))
      (node (ref "IC1") (pin "57") (pinfunction "VDDIO_57") (pintype "bidirectional"))
      (node (ref "IC1") (pin "85") (pinfunction "VDDCSI_85") (pintype "bidirectional"))
      (node (ref "IC1") (pin "93") (pinfunction "VCCETH_93") (pintype "bidirectional"))
      (node (ref "IC3") (pin "13") (pinfunction "LDVIN24_13") (pintype "bidirectional"))
      (node (ref "IC3") (pin "17") (pinfunction "FB3_17") (pintype "bidirectional"))
      (node (ref "IC3") (pin "40") (pinfunction "LDVIN3_40") (pintype "bidirectional"))
      (node (ref "J2") (pin "4") (pinfunction "VCC_4") (pintype "power_in"))
      (node (ref "L4") (pin "1") (pinfunction "1_1") (pintype "passive"))
    )
    (net (code "45") (name "VCORE") (class "Default")
      (node (ref "C11") (pin "1") (pinfunction "1_1") (pintype "passive"))
      (node (ref "C12") (pin "1") (pinfunction "1_1") (pintype "passive"))
      (node (ref "C13") (pin "1") (pinfunction "1_1") (pintype "passive"))
      (node (ref "C14") (pin "1") (pinfunction "1_1") (pintype "passive"))
      (node (ref "C15") (pin "1") (pinfunction "1_1") (pintype "passive"))
      (node (ref "C16") (pin "1") (pinfunction "1_1") (pintype "passive"))
      (node (ref "C36") (pin "1") (pinfunction "1_1") (pintype "passive"))
      (node (ref "IC1") (pin "108") (pinfunction "VDDSYS_108") (pintype "bidirectional"))
      (node (ref "IC1") (pin "126") (pinfunction "VDDSYS_126") (pintype "bidirectional"))
      (node (ref "IC1") (pin "19") (pinfunction "VDDSYS_19") (pintype "bidirectional"))
      (node (ref "IC1") (pin "20") (pinfunction "VCORE_20") (pintype "bidirectional"))
      (node (ref "IC1") (pin "21") (pinfunction "VCORE_21") (pintype "bidirectional"))
      (node (ref "IC1") (pin "25") (pinfunction "VCORE_25") (pintype "bidirectional"))
      (node (ref "IC1") (pin "26") (pinfunction "VCORE_26") (pintype "bidirectional"))
      (node (ref "IC1") (pin "38") (pinfunction "VCORE_38") (pintype "bidirectional"))
      (node (ref "IC1") (pin "47") (pinfunction "VCORE_47") (pintype "bidirectional"))
      (node (ref "IC1") (pin "51") (pinfunction "VCORE_51") (pintype "bidirectional"))
      (node (ref "IC1") (pin "56") (pinfunction "VCORE_56") (pintype "bidirectional"))
      (node (ref "IC1") (pin "58") (pinfunction "VDDSYS_58") (pintype "bidirectional"))
      (node (ref "IC1") (pin "64") (pinfunction "VDDSYS_64") (pintype "bidirectional"))
      (node (ref "IC1") (pin "80") (pinfunction "VDDSYS_80") (pintype "bidirectional"))
      (node (ref "IC1") (pin "88") (pinfunction "VDDETH_88") (pintype "bidirectional"))
      (node (ref "IC3") (pin "10") (pinfunction "FB2_10") (pintype "bidirectional"))
      (node (ref "L3") (pin "1") (pinfunction "1_1") (pintype "passive"))
    )
    (net (code "46") (name "VDD") (class "Default")
      (node (ref "C10") (pin "1") (pinfunction "1_1") (pintype "passive"))
      (node (ref "C32") (pin "1") (pinfunction "1_1") (pintype "passive"))
      (node (ref "C37") (pin "1") (pinfunction "1_1") (pintype "passive"))
      (node (ref "IC1") (pin "122") (pinfunction "AVDDP_122") (pintype "bidirectional"))
      (node (ref "IC2") (pin "1") (pinfunction "VIN_1") (pintype "input"))
      (node (ref "IC2") (pin "3") (pinfunction "CE_3") (pintype "input"))
      (node (ref "IC3") (pin "14") (pinfunction "VIN3_14") (pintype "bidirectional"))
      (node (ref "IC3") (pin "21") (pinfunction "AVCC_21") (pintype "bidirectional"))
      (node (ref "IC3") (pin "29") (pinfunction "CONFIG3_29") (pintype "bidirectional"))
      (node (ref "IC3") (pin "34") (pinfunction "IPSOUT_34") (pintype "bidirectional"))
      (node (ref "IC3") (pin "35") (pinfunction "IPSOUT_35") (pintype "bidirectional"))
      (node (ref "IC3") (pin "44") (pinfunction "VIN1_44") (pintype "bidirectional"))
      (node (ref "IC3") (pin "7") (pinfunction "VIN2_7") (pintype "bidirectional"))
      (node (ref "RESET") (pin "1") (pinfunction "1_1") (pintype "passive"))
      (node (ref "RN1") (pin "2") (pinfunction "1_2") (pintype "passive"))
      (node (ref "RN1") (pin "3") (pinfunction "1_3") (pintype "passive"))
      (node (ref "RN1") (pin "4") (pinfunction "1_4") (pintype "passive"))
    )
    (net (code "47") (name "unconnected-(IC1E-PF6-Pad100)") (class "Default")
      (node (ref "IC1") (pin "100") (pinfunction "PF6_100") (pintype "bidirectional"))
    )
    (net (code "48") (name "unconnected-(IC1E-PG0{slash}SD1_CLK-Pad5)") (class "Default")
      (node (ref "IC1") (pin "5") (pinfunction "PG0/SD1_CLK_5") (pintype "bidirectional"))
    )
    (net (code "49") (name "unconnected-(IC1E-PG1{slash}SD1_CMD-Pad4)") (class "Default")
      (node (ref "IC1") (pin "4") (pinfunction "PG1/SD1_CMD_4") (pintype "bidirectional"))
    )
    (net (code "50") (name "unconnected-(IC1E-PG2{slash}SD1_D0-Pad3)") (class "Default")
      (node (ref "IC1") (pin "3") (pinfunction "PG2/SD1_D0_3") (pintype "bidirectional"))
    )
    (net (code "51") (name "unconnected-(IC1E-PG3{slash}SD1_D1-Pad2)") (class "Default")
      (node (ref "IC1") (pin "2") (pinfunction "PG3/SD1_D1_2") (pintype "bidirectional"))
    )
    (net (code "52") (name "unconnected-(IC1E-PG4{slash}SD1_D2-Pad1)") (class "Default")
      (node (ref "IC1") (pin "1") (pinfunction "PG4/SD1_D2_1") (pintype "bidirectional"))
    )
    (net (code "53") (name "unconnected-(IC1E-PG5{slash}SD1_D3-Pad128)") (class "Default")
      (node (ref "IC1") (pin "128") (pinfunction "PG5/SD1_D3_128") (pintype "bidirectional"))
    )
    (net (code "54") (name "unconnected-(IC3-BACKUP-Pad30)") (class "Default")
      (node (ref "IC3") (pin "30") (pinfunction "BACKUP_30") (pintype "bidirectional"))
    )
    (net (code "55") (name "unconnected-(IC3-EXTEN-Pad20)") (class "Default")
      (node (ref "IC3") (pin "20") (pinfunction "EXTEN_20") (pintype "bidirectional"))
    )
    (net (code "56") (name "unconnected-(IC3-GPIO0{slash}LDEN0-Pad19)") (class "Default")
      (node (ref "IC3") (pin "19") (pinfunction "GPIO0/LDEN0_19") (pintype "bidirectional"))
    )
    (net (code "57") (name "unconnected-(IC3-GPIO1-Pad18)") (class "Default")
      (node (ref "IC3") (pin "18") (pinfunction "GPIO1_18") (pintype "bidirectional"))
    )
    (net (code "58") (name "unconnected-(IC3-GPIO2-Pad5)") (class "Default")
      (node (ref "IC3") (pin "5") (pinfunction "GPIO2_5") (pintype "bidirectional"))
    )
    (net (code "59") (name "unconnected-(IC3-GPIO3-Pad3)") (class "Default")
      (node (ref "IC3") (pin "3") (pinfunction "GPIO3_3") (pintype "bidirectional"))
    )
    (net (code "60") (name "unconnected-(IC3-~{CHARGE}-Pad36)") (class "Default")
      (node (ref "IC3") (pin "36") (pinfunction "~{CHARGE}_36") (pintype "bidirectional"))
    )
    (net (code "61") (name "unconnected-(J2-DETECT-Pad9)") (class "Default")
      (node (ref "J2") (pin "9") (pinfunction "DETECT_9") (pintype "passive"))
    )
    (net (code "62") (name "~{IRQ}") (class "Default")
      (node (ref "IC3") (pin "48") (pinfunction "~{IRQ}_48") (pintype "bidirectional"))
      (node (ref "RN1") (pin "7") (pinfunction "2_7") (pintype "passive"))
    )
    (net (code "63") (name "~{RESET}") (class "Default")
      (node (ref "IC1") (pin "99") (pinfunction "~{RESET}_99") (pintype "bidirectional"))
      (node (ref "R8") (pin "1") (pinfunction "1_1") (pintype "passive"))
    )
    (net (code "64") (name "~{VBUSEN}") (class "Default")
      (node (ref "IC3") (pin "6") (pinfunction "~{VBUSEN}_6") (pintype "bidirectional"))
    )
  )
)
